# UART_CH340G.net
KiCad netlist of a schematic drawn in Altium Designer
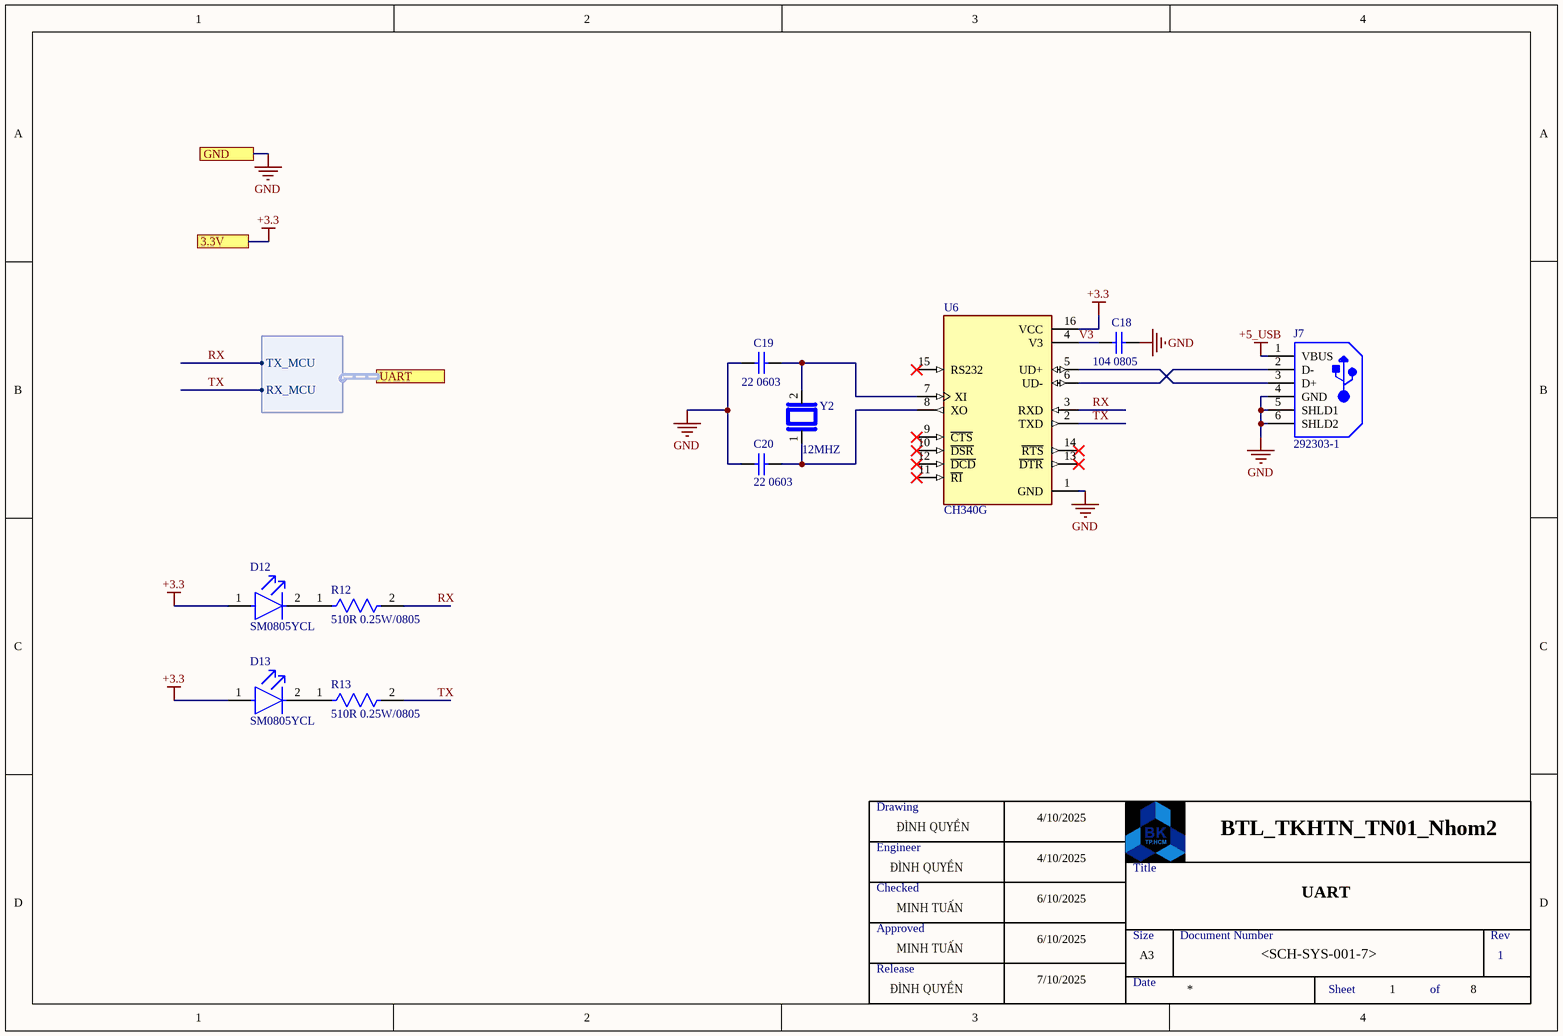
[diagram p0: UART_CH340G.SchDoc]

(export (version "E")
  (design (tool "Eeschema 10.0.6"))
  (components
    (comp (ref "C18")
      (value "104 0805")
      (footprint "CAPC0805(2012)145_M")
      (description "CAP 15nF 100V ±10% 0805 (2012 Metric) Thickness 1.45mm SMD")
      (fields (field (name "TOLERANCE") "Â±10%"))
      (libsource (lib "Altium Content Vault") (part "CAP"))
    )
    (comp (ref "C19")
      (value "22 0603")
      (footprint "CAPC1608X92X38ML15T08")
      (fields (field (name "MANUFACTURER") "Vitramon") (field (name "PART NUMBER") "VJ0603Y103JXXAC"))
      (libsource (lib "Altium Content Vault") (part "CAP"))
    )
    (comp (ref "C20")
      (value "22 0603")
      (footprint "CAPC1608X92X38ML15T08")
      (fields (field (name "MANUFACTURER") "Vitramon") (field (name "PART NUMBER") "VJ0603Y103JXXAC"))
      (libsource (lib "Altium Content Vault") (part "CAP"))
    )
    (comp (ref "D12")
      (value "SM0805YCL")
      (footprint "FP-SM0805YCL-MFG")
      (description "LED YELLOW CLEAR 0805 SMD")
      (libsource (lib "Altium Content Vault") (part "ab1c01a81903e929fc6c44469aada92"))
    )
    (comp (ref "D13")
      (value "SM0805YCL")
      (footprint "FP-SM0805YCL-MFG")
      (description "LED YELLOW CLEAR 0805 SMD")
      (libsource (lib "Altium Content Vault") (part "ab1c01a81903e929fc6c44469aada92"))
    )
    (comp (ref "J7")
      (value "292303-1")
      (footprint "TE-292303-1_V")
      (fields (field (name "MANUFACTURER") "TE Connectivity"))
      (libsource (lib "Altium Content Vault") (part "USB-4-2SHLD"))
    )
    (comp (ref "R12")
      (value "510R 0.25W/0805")
      (footprint "FP-AF0805-IPC_C")
      (description "Anti-Sulfurated Chip Resistor Automotive Grade 75Ω 1% 0.125W ±100ppm/°C 0805")
      (fields (field (name "TOLERANCE") "1%"))
      (libsource (lib "Altium Content Vault") (part "1029c3af85768c4190bb7ad29bc67b5"))
    )
    (comp (ref "R13")
      (value "510R 0.25W/0805")
      (footprint "FP-AF0805-IPC_C")
      (description "Anti-Sulfurated Chip Resistor Automotive Grade 75Ω 1% 0.125W ±100ppm/°C 0805")
      (fields (field (name "TOLERANCE") "1%"))
      (libsource (lib "Altium Content Vault") (part "1029c3af85768c4190bb7ad29bc67b5"))
    )
    (comp (ref "U6")
      (value "CH340G")
      (footprint "SOIC127P600X180-16N")
      (description "USB Interface Integrated Circuit")
      (fields (field (name "MP") "Ch340G") (field (name "MF") "WCH"))
      (libsource (lib "CH340G") (part "CH340G"))
    )
    (comp (ref "Y2")
      (value "12MHZ")
      (footprint "XTAL_HC49P488W43L1150T466H350")
      (description "16 MHz Â±30ppm Crystal 18pF 50 Ohms HC-49/US")
      (fields (field (name "MF") "Citizen Finedevice") (field (name "MP") "HC-49/U-S16000000ABJB"))
      (libsource (lib "HC-49_U-S16000000ABJB") (part "HC-49/U-S16000000ABJB"))
    )
  )
  (nets
    (net (code "2") (name "+3.3") (class "Default")
      (node (ref "D12") (pin "1") (pinfunction "A_1") (pintype "passive"))
      (node (ref "D13") (pin "1") (pinfunction "A_1") (pintype "passive"))
      (node (ref "U6") (pin "16") (pinfunction "VCC_16") (pintype "power_in"))
    )
    (net (code "3") (name "+5_USB") (class "Default")
      (node (ref "J7") (pin "1") (pinfunction "VBUS_1") (pintype "passive"))
    )
    (net (code "4") (name "/RX") (class "Default")
      (node (ref "R12") (pin "2") (pinfunction "2_2") (pintype "passive"))
      (node (ref "U6") (pin "3") (pinfunction "RXD_3") (pintype "input"))
    )
    (net (code "5") (name "/TX") (class "Default")
      (node (ref "R13") (pin "2") (pinfunction "2_2") (pintype "passive"))
      (node (ref "U6") (pin "2") (pinfunction "TXD_2") (pintype "output"))
    )
    (net (code "6") (name "/V3") (class "Default")
      (node (ref "C18") (pin "1") (pinfunction "1_1") (pintype "passive"))
      (node (ref "U6") (pin "4") (pinfunction "V3_4") (pintype "power_in"))
    )
    (net (code "8") (name "GND") (class "Default")
      (node (ref "C18") (pin "2") (pinfunction "2_2") (pintype "passive"))
      (node (ref "C19") (pin "2") (pinfunction "2_2") (pintype "passive"))
      (node (ref "C20") (pin "2") (pinfunction "2_2") (pintype "passive"))
      (node (ref "J7") (pin "4") (pinfunction "GND_4") (pintype "passive"))
      (node (ref "J7") (pin "5") (pinfunction "SHLD1_5") (pintype "passive"))
      (node (ref "J7") (pin "6") (pinfunction "SHLD2_6") (pintype "passive"))
      (node (ref "U6") (pin "1") (pinfunction "GND_1") (pintype "power_in"))
    )
    (net (code "9") (name "Net-(D12-C)") (class "Default")
      (node (ref "D12") (pin "2") (pinfunction "C_2") (pintype "passive"))
      (node (ref "R12") (pin "1") (pinfunction "1_1") (pintype "passive"))
    )
    (net (code "10") (name "Net-(D13-C)") (class "Default")
      (node (ref "D13") (pin "2") (pinfunction "C_2") (pintype "passive"))
      (node (ref "R13") (pin "1") (pinfunction "1_1") (pintype "passive"))
    )
    (net (code "11") (name "Net-(J7-D+)") (class "Default")
      (node (ref "J7") (pin "3") (pinfunction "D+_3") (pintype "passive"))
      (node (ref "U6") (pin "5") (pinfunction "UD+_5") (pintype "bidirectional"))
    )
    (net (code "12") (name "Net-(J7-D-)") (class "Default")
      (node (ref "J7") (pin "2") (pinfunction "D-_2") (pintype "passive"))
      (node (ref "U6") (pin "6") (pinfunction "UD-_6") (pintype "bidirectional"))
    )
    (net (code "13") (name "Net-(U6-XI)") (class "Default")
      (node (ref "C19") (pin "1") (pinfunction "1_1") (pintype "passive"))
      (node (ref "U6") (pin "7") (pinfunction "XI_7") (pintype "input"))
      (node (ref "Y2") (pin "2") (pinfunction "2_2") (pintype "passive"))
    )
    (net (code "14") (name "Net-(U6-XO)") (class "Default")
      (node (ref "C20") (pin "1") (pinfunction "1_1") (pintype "passive"))
      (node (ref "U6") (pin "8") (pinfunction "XO_8") (pintype "output"))
      (node (ref "Y2") (pin "1") (pinfunction "1_1") (pintype "passive"))
    )
    (net (code "15") (name "unconnected-(U6-RS232-Pad15)") (class "Default")
      (node (ref "U6") (pin "15") (pinfunction "RS232_15") (pintype "input+no_connect"))
    )
    (net (code "16") (name "unconnected-(U6-~{CTS}-Pad9)") (class "Default")
      (node (ref "U6") (pin "9") (pinfunction "~{CTS}_9") (pintype "input+no_connect"))
    )
    (net (code "17") (name "unconnected-(U6-~{DCD}-Pad12)") (class "Default")
      (node (ref "U6") (pin "12") (pinfunction "~{DCD}_12") (pintype "input+no_connect"))
    )
    (net (code "18") (name "unconnected-(U6-~{DSR}-Pad10)") (class "Default")
      (node (ref "U6") (pin "10") (pinfunction "~{DSR}_10") (pintype "input+no_connect"))
    )
    (net (code "19") (name "unconnected-(U6-~{DTR}-Pad13)") (class "Default")
      (node (ref "U6") (pin "13") (pinfunction "~{DTR}_13") (pintype "output+no_connect"))
    )
    (net (code "20") (name "unconnected-(U6-~{RI}-Pad11)") (class "Default")
      (node (ref "U6") (pin "11") (pinfunction "~{RI}_11") (pintype "input+no_connect"))
    )
    (net (code "21") (name "unconnected-(U6-~{RTS}-Pad14)") (class "Default")
      (node (ref "U6") (pin "14") (pinfunction "~{RTS}_14") (pintype "output+no_connect"))
    )
  )
)
